# SPE_Electronics.net
KiCad netlist of a schematic drawn in Altium Designer
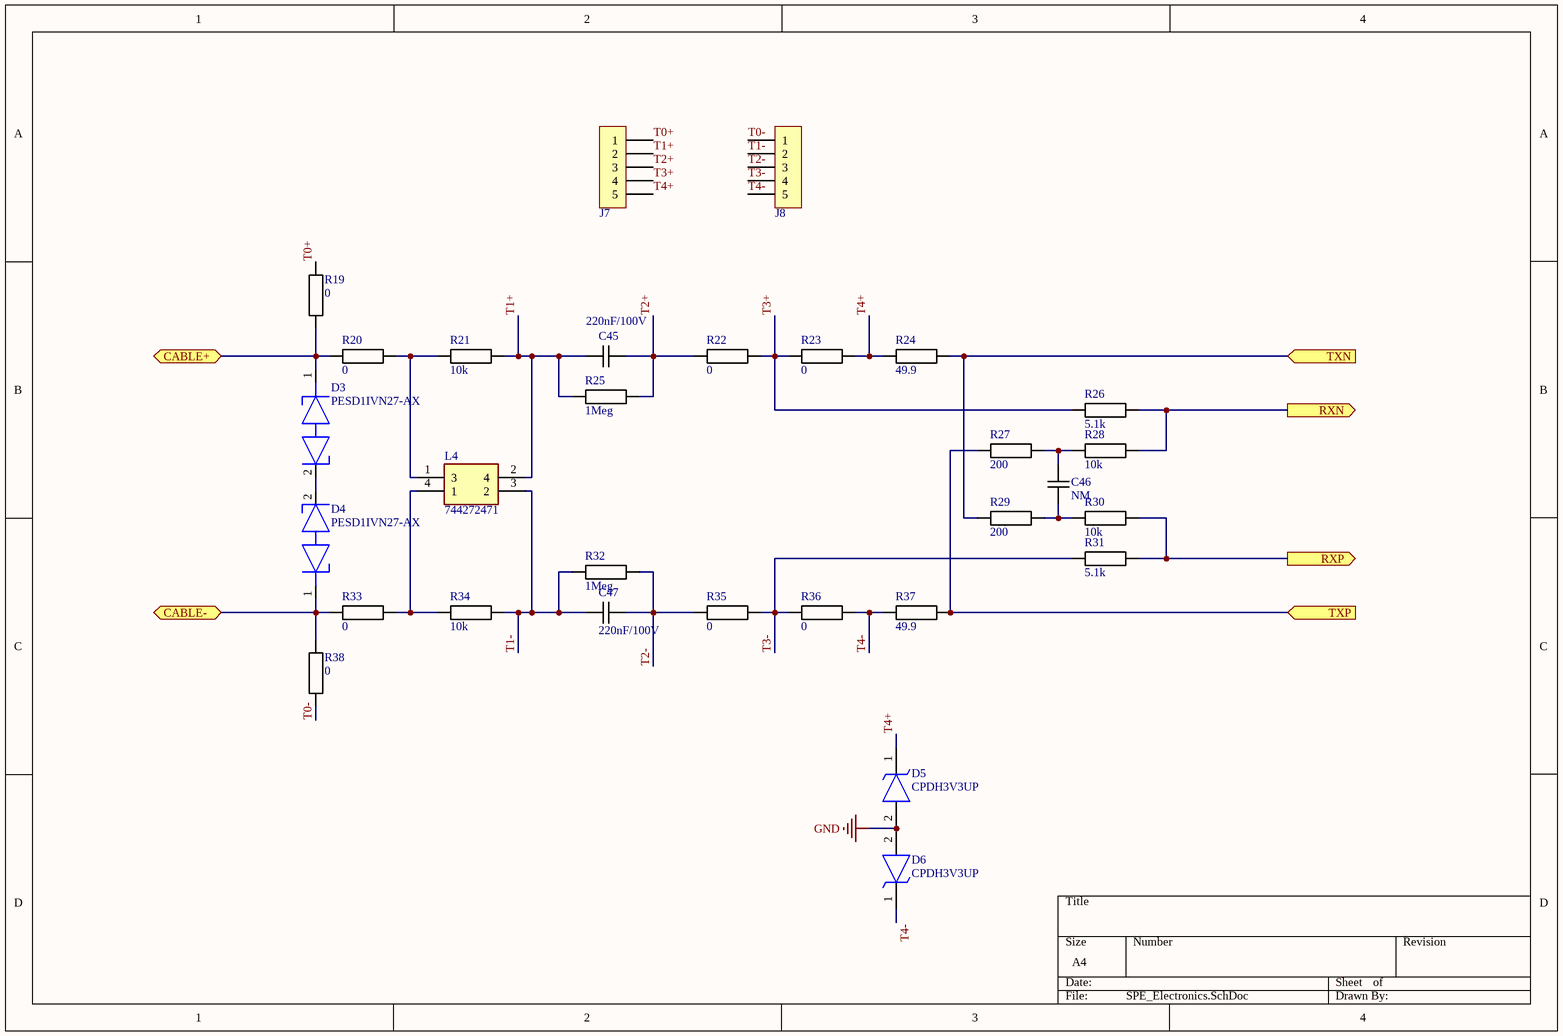
[diagram p0: SPE_Electronics.SchDoc]

(export (version "E")
  (design (tool "Eeschema 10.0.6"))
  (components
    (comp (ref "C45")
      (value "220nF/100V")
      (footprint "CAPACITOR 1608 REFLOW")
      (description "Capacitor")
      (libsource (lib "Capacitor") (part "Capacitor"))
    )
    (comp (ref "C46")
      (value "NM")
      (footprint "CAPACITOR 1608 REFLOW")
      (description "Capacitor")
      (libsource (lib "Capacitor") (part "Capacitor"))
    )
    (comp (ref "C47")
      (value "220nF/100V")
      (footprint "CAPACITOR 1608 REFLOW")
      (description "Capacitor")
      (libsource (lib "Capacitor") (part "Capacitor"))
    )
    (comp (ref "D3")
      (value "PESD1IVN27-AX")
      (footprint "PESD1IVN27AX")
      (description "Diode ESD (Bi-directional)")
      (fields (field (name "MOUSER PART NUMBER") "771-PESD1IVN27-AX"))
      (libsource (lib "*") (part "PESD1IVN27-AX"))
    )
    (comp (ref "D4")
      (value "PESD1IVN27-AX")
      (footprint "PESD1IVN27AX")
      (description "Diode ESD (Bi-directional)")
      (fields (field (name "MOUSER PART NUMBER") "771-PESD1IVN27-AX"))
      (libsource (lib "*") (part "PESD1IVN27-AX"))
    )
    (comp (ref "D5")
      (value "CPDH3V3UP")
      (footprint "CPDH3V3UP")
      (description "TVS Diode (Uni-directional)")
      (fields (field (name "MOUSER PART NUMBER") "750-CPDH3V3UP"))
      (libsource (lib "SamacSys") (part "CPDH3V3UP"))
    )
    (comp (ref "D6")
      (value "CPDH3V3UP")
      (footprint "CPDH3V3UP")
      (description "TVS Diode (Uni-directional)")
      (fields (field (name "MOUSER PART NUMBER") "750-CPDH3V3UP"))
      (libsource (lib "*") (part "CPDH3V3UP"))
    )
    (comp (ref "J7")
      (value "*")
      (footprint "PinHeader1x5 P2.54")
      (description "Plug connector")
      (libsource (lib "") (part "PinHeader1x5_1"))
    )
    (comp (ref "J8")
      (value "*")
      (footprint "PinHeader1x5 P2.54")
      (description "Plug connector")
      (libsource (lib "PinHeader") (part "PinHeader1x5"))
    )
    (comp (ref "L4")
      (value "744272471")
      (footprint "WE-SL575")
      (description "Inductor")
      (fields (field (name "MOUSER PART NUMBER") "710-744272471"))
      (libsource (lib "*") (part "744272471"))
    )
    (comp (ref "R19")
      (value "0")
      (footprint "RESISTOR 1608 REFLOW")
      (description "Resistor")
      (libsource (lib "Resistor") (part "Resistor"))
    )
    (comp (ref "R20")
      (value "0")
      (footprint "RESISTOR 1608 REFLOW")
      (description "Resistor")
      (libsource (lib "Resistor") (part "Resistor"))
    )
    (comp (ref "R21")
      (value "10k")
      (footprint "RESISTOR 1608 REFLOW")
      (description "Resistor")
      (libsource (lib "Resistor") (part "Resistor"))
    )
    (comp (ref "R22")
      (value "0")
      (footprint "RESISTOR 1608 REFLOW")
      (description "Resistor")
      (libsource (lib "Resistor") (part "Resistor"))
    )
    (comp (ref "R23")
      (value "0")
      (footprint "RESISTOR 1608 REFLOW")
      (description "Resistor")
      (libsource (lib "Resistor") (part "Resistor"))
    )
    (comp (ref "R24")
      (value "49.9")
      (footprint "RESISTOR 1608 REFLOW")
      (description "Resistor")
      (libsource (lib "Resistor") (part "Resistor"))
    )
    (comp (ref "R25")
      (value "1Meg")
      (footprint "RESISTOR 1608 REFLOW")
      (description "Resistor")
      (libsource (lib "Resistor") (part "Resistor"))
    )
    (comp (ref "R26")
      (value "5.1k")
      (footprint "RESISTOR 1608 REFLOW")
      (description "Resistor")
      (libsource (lib "Resistor") (part "Resistor"))
    )
    (comp (ref "R27")
      (value "200")
      (footprint "RESISTOR 1608 REFLOW")
      (description "Resistor")
      (libsource (lib "Resistor") (part "Resistor"))
    )
    (comp (ref "R28")
      (value "10k")
      (footprint "RESISTOR 1608 REFLOW")
      (description "Resistor")
      (libsource (lib "Resistor") (part "Resistor"))
    )
    (comp (ref "R29")
      (value "200")
      (footprint "RESISTOR 1608 REFLOW")
      (description "Resistor")
      (libsource (lib "Resistor") (part "Resistor"))
    )
    (comp (ref "R30")
      (value "10k")
      (footprint "RESISTOR 1608 REFLOW")
      (description "Resistor")
      (libsource (lib "Resistor") (part "Resistor"))
    )
    (comp (ref "R31")
      (value "5.1k")
      (footprint "RESISTOR 1608 REFLOW")
      (description "Resistor")
      (libsource (lib "Resistor") (part "Resistor"))
    )
    (comp (ref "R32")
      (value "1Meg")
      (footprint "RESISTOR 1608 REFLOW")
      (description "Resistor")
      (libsource (lib "Resistor") (part "Resistor"))
    )
    (comp (ref "R33")
      (value "0")
      (footprint "RESISTOR 1608 REFLOW")
      (description "Resistor")
      (libsource (lib "Resistor") (part "Resistor"))
    )
    (comp (ref "R34")
      (value "10k")
      (footprint "RESISTOR 1608 REFLOW")
      (description "Resistor")
      (libsource (lib "Resistor") (part "Resistor"))
    )
    (comp (ref "R35")
      (value "0")
      (footprint "RESISTOR 1608 REFLOW")
      (description "Resistor")
      (libsource (lib "Resistor") (part "Resistor"))
    )
    (comp (ref "R36")
      (value "0")
      (footprint "RESISTOR 1608 REFLOW")
      (description "Resistor")
      (libsource (lib "Resistor") (part "Resistor"))
    )
    (comp (ref "R37")
      (value "49.9")
      (footprint "RESISTOR 1608 REFLOW")
      (description "Resistor")
      (libsource (lib "Resistor") (part "Resistor"))
    )
    (comp (ref "R38")
      (value "0")
      (footprint "RESISTOR 1608 REFLOW")
      (description "Resistor")
      (libsource (lib "Resistor") (part "Resistor"))
    )
  )
  (nets
    (net (code "1") (name "/CABLE+") (class "Default")
      (node (ref "D3") (pin "1") (pinfunction "K1_1") (pintype "passive"))
      (node (ref "R19") (pin "2") (pinfunction "2_2") (pintype "passive"))
      (node (ref "R20") (pin "2") (pinfunction "2_2") (pintype "passive"))
    )
    (net (code "2") (name "/CABLE-") (class "Default")
      (node (ref "D4") (pin "1") (pinfunction "K1_1") (pintype "passive"))
      (node (ref "R33") (pin "2") (pinfunction "2_2") (pintype "passive"))
      (node (ref "R38") (pin "2") (pinfunction "2_2") (pintype "passive"))
    )
    (net (code "3") (name "/RXN") (class "Default")
      (node (ref "R26") (pin "1") (pinfunction "1_1") (pintype "passive"))
      (node (ref "R28") (pin "1") (pinfunction "1_1") (pintype "passive"))
    )
    (net (code "4") (name "/RXP") (class "Default")
      (node (ref "R30") (pin "1") (pinfunction "1_1") (pintype "passive"))
      (node (ref "R31") (pin "1") (pinfunction "1_1") (pintype "passive"))
    )
    (net (code "5") (name "/T0+") (class "Default")
      (node (ref "J7") (pin "1") (pinfunction "1_1") (pintype "passive"))
      (node (ref "R19") (pin "1") (pinfunction "1_1") (pintype "passive"))
    )
    (net (code "6") (name "/T0-") (class "Default")
      (node (ref "J8") (pin "1") (pinfunction "1_1") (pintype "passive"))
      (node (ref "R38") (pin "1") (pinfunction "1_1") (pintype "passive"))
    )
    (net (code "7") (name "/T1+") (class "Default")
      (node (ref "C45") (pin "2") (pinfunction "2_2") (pintype "passive"))
      (node (ref "J7") (pin "2") (pinfunction "2_2") (pintype "passive"))
      (node (ref "L4") (pin "2") (pinfunction "4_2") (pintype "passive"))
      (node (ref "R21") (pin "1") (pinfunction "1_1") (pintype "passive"))
      (node (ref "R25") (pin "2") (pinfunction "2_2") (pintype "passive"))
    )
    (net (code "8") (name "/T1-") (class "Default")
      (node (ref "C47") (pin "2") (pinfunction "2_2") (pintype "passive"))
      (node (ref "J8") (pin "2") (pinfunction "2_2") (pintype "passive"))
      (node (ref "L4") (pin "3") (pinfunction "2_3") (pintype "passive"))
      (node (ref "R32") (pin "2") (pinfunction "2_2") (pintype "passive"))
      (node (ref "R34") (pin "1") (pinfunction "1_1") (pintype "passive"))
    )
    (net (code "9") (name "/T2+") (class "Default")
      (node (ref "C45") (pin "1") (pinfunction "1_1") (pintype "passive"))
      (node (ref "J7") (pin "3") (pinfunction "3_3") (pintype "passive"))
      (node (ref "R22") (pin "2") (pinfunction "2_2") (pintype "passive"))
      (node (ref "R25") (pin "1") (pinfunction "1_1") (pintype "passive"))
    )
    (net (code "10") (name "/T2-") (class "Default")
      (node (ref "C47") (pin "1") (pinfunction "1_1") (pintype "passive"))
      (node (ref "J8") (pin "3") (pinfunction "3_3") (pintype "passive"))
      (node (ref "R32") (pin "1") (pinfunction "1_1") (pintype "passive"))
      (node (ref "R35") (pin "2") (pinfunction "2_2") (pintype "passive"))
    )
    (net (code "11") (name "/T3+") (class "Default")
      (node (ref "J7") (pin "4") (pinfunction "4_4") (pintype "passive"))
      (node (ref "R22") (pin "1") (pinfunction "1_1") (pintype "passive"))
      (node (ref "R23") (pin "2") (pinfunction "2_2") (pintype "passive"))
      (node (ref "R26") (pin "2") (pinfunction "2_2") (pintype "passive"))
    )
    (net (code "12") (name "/T3-") (class "Default")
      (node (ref "J8") (pin "4") (pinfunction "4_4") (pintype "passive"))
      (node (ref "R31") (pin "2") (pinfunction "2_2") (pintype "passive"))
      (node (ref "R35") (pin "1") (pinfunction "1_1") (pintype "passive"))
      (node (ref "R36") (pin "2") (pinfunction "2_2") (pintype "passive"))
    )
    (net (code "13") (name "/T4+") (class "Default")
      (node (ref "D5") (pin "1") (pinfunction "K_1") (pintype "passive"))
      (node (ref "J7") (pin "5") (pinfunction "5_5") (pintype "passive"))
      (node (ref "R23") (pin "1") (pinfunction "1_1") (pintype "passive"))
      (node (ref "R24") (pin "2") (pinfunction "2_2") (pintype "passive"))
    )
    (net (code "14") (name "/T4-") (class "Default")
      (node (ref "D6") (pin "1") (pinfunction "K_1") (pintype "passive"))
      (node (ref "J8") (pin "5") (pinfunction "5_5") (pintype "passive"))
      (node (ref "R36") (pin "1") (pinfunction "1_1") (pintype "passive"))
      (node (ref "R37") (pin "2") (pinfunction "2_2") (pintype "passive"))
    )
    (net (code "15") (name "/TXN") (class "Default")
      (node (ref "R24") (pin "1") (pinfunction "1_1") (pintype "passive"))
      (node (ref "R29") (pin "2") (pinfunction "2_2") (pintype "passive"))
    )
    (net (code "16") (name "/TXP") (class "Default")
      (node (ref "R27") (pin "2") (pinfunction "2_2") (pintype "passive"))
      (node (ref "R37") (pin "1") (pinfunction "1_1") (pintype "passive"))
    )
    (net (code "17") (name "GND") (class "Default")
      (node (ref "D5") (pin "2") (pinfunction "A_2") (pintype "passive"))
      (node (ref "D6") (pin "2") (pinfunction "A_2") (pintype "passive"))
    )
    (net (code "18") (name "Net-(C46-Pad1)") (class "Default")
      (node (ref "C46") (pin "1") (pinfunction "1_1") (pintype "passive"))
      (node (ref "R29") (pin "1") (pinfunction "1_1") (pintype "passive"))
      (node (ref "R30") (pin "2") (pinfunction "2_2") (pintype "passive"))
    )
    (net (code "19") (name "Net-(C46-Pad2)") (class "Default")
      (node (ref "C46") (pin "2") (pinfunction "2_2") (pintype "passive"))
      (node (ref "R27") (pin "1") (pinfunction "1_1") (pintype "passive"))
      (node (ref "R28") (pin "2") (pinfunction "2_2") (pintype "passive"))
    )
    (net (code "20") (name "Net-(D3-K2)") (class "Default")
      (node (ref "D3") (pin "2") (pinfunction "K2_2") (pintype "passive"))
      (node (ref "D4") (pin "2") (pinfunction "K2_2") (pintype "passive"))
    )
    (net (code "21") (name "Net-(L4-1)") (class "Default")
      (node (ref "L4") (pin "4") (pinfunction "1_4") (pintype "passive"))
      (node (ref "R33") (pin "1") (pinfunction "1_1") (pintype "passive"))
      (node (ref "R34") (pin "2") (pinfunction "2_2") (pintype "passive"))
    )
    (net (code "22") (name "Net-(L4-3)") (class "Default")
      (node (ref "L4") (pin "1") (pinfunction "3_1") (pintype "passive"))
      (node (ref "R20") (pin "1") (pinfunction "1_1") (pintype "passive"))
      (node (ref "R21") (pin "2") (pinfunction "2_2") (pintype "passive"))
    )
  )
)
